# Relay_Driver_V1_1.net
KiCad netlist of a schematic drawn in EAGLE
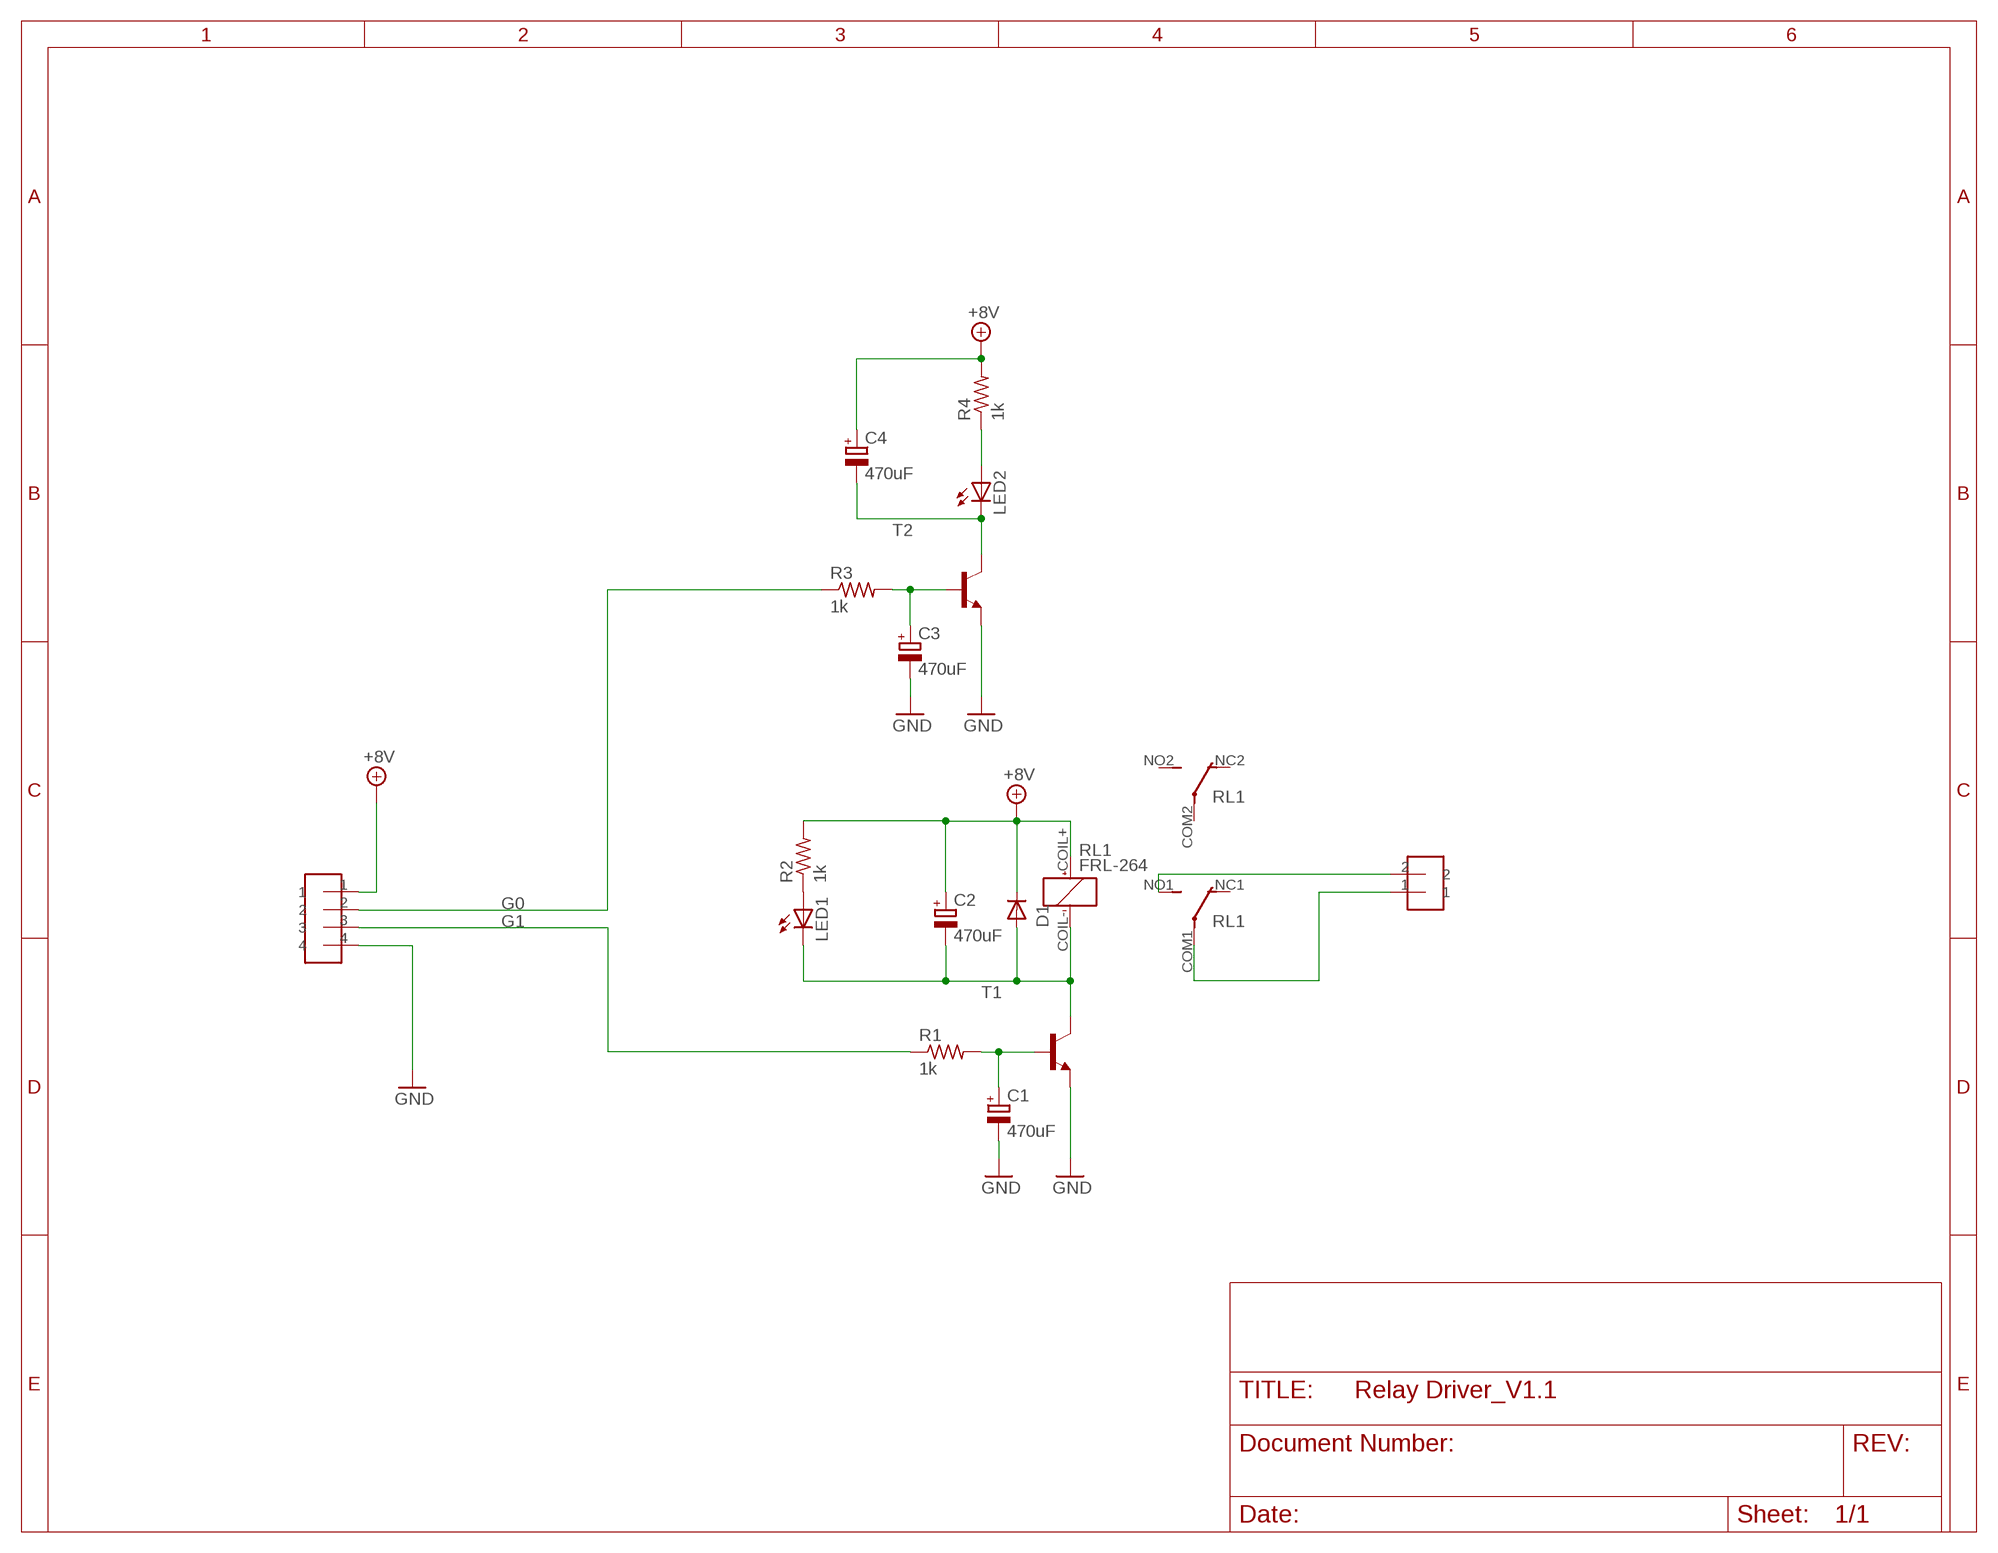
[diagram p0: schematic, sheet 1]

(export (version "E")
  (design (tool "Eeschema 10.0.6"))
  (components
    (comp (ref "C1")
      (value "470uF")
      (footprint "eagle-import:E3,5-10")
      (libsource (lib "eagle-import") (part "CPOL-EUE3.5-10"))
    )
    (comp (ref "C2")
      (value "470uF")
      (footprint "eagle-import:E3,5-10")
      (libsource (lib "eagle-import") (part "CPOL-EUE3.5-10"))
    )
    (comp (ref "C3")
      (value "470uF")
      (footprint "eagle-import:E3,5-10")
      (libsource (lib "eagle-import") (part "CPOL-EUE3.5-10"))
    )
    (comp (ref "C4")
      (value "470uF")
      (footprint "eagle-import:E3,5-10")
      (libsource (lib "eagle-import") (part "CPOL-EUE3.5-10"))
    )
    (comp (ref "D1")
      (value "1N4148DO35-10")
      (footprint "eagle-import:DO35-10")
      (libsource (lib "eagle-import") (part "1N4148DO35-10"))
    )
    (comp (ref "LED1")
      (value "LED5MM")
      (footprint "eagle-import:LED5MM")
      (libsource (lib "eagle-import") (part "LED5MM"))
    )
    (comp (ref "LED2")
      (value "LED5MM")
      (footprint "eagle-import:LED5MM")
      (libsource (lib "eagle-import") (part "LED5MM"))
    )
    (comp (ref "R1")
      (value "1k")
      (footprint "eagle-import:P0613V")
      (libsource (lib "eagle-import") (part "R-US_0613/5V"))
    )
    (comp (ref "R2")
      (value "1k")
      (footprint "eagle-import:P0613V")
      (libsource (lib "eagle-import") (part "R-US_0613/5V"))
    )
    (comp (ref "R3")
      (value "1k")
      (footprint "eagle-import:P0613V")
      (libsource (lib "eagle-import") (part "R-US_0613/5V"))
    )
    (comp (ref "R4")
      (value "1k")
      (footprint "eagle-import:P0613V")
      (libsource (lib "eagle-import") (part "R-US_0613/5V"))
    )
    (comp (ref "RL1")
      (value "FRL-264")
      (footprint "eagle-import:FRL-264")
      (libsource (lib "eagle-import") (part "FRL-264"))
    )
    (comp (ref "T1")
      (value "-NPN-TO92-EBC")
      (footprint "eagle-import:TO92-EBC")
      (libsource (lib "eagle-import") (part "-NPN-TO92-EBC"))
    )
    (comp (ref "T2")
      (value "-NPN-TO92-EBC")
      (footprint "eagle-import:TO92-EBC")
      (libsource (lib "eagle-import") (part "-NPN-TO92-EBC"))
    )
    (comp (ref "U$1")
      (value "1X4HEADER_100MIL")
      (footprint "eagle-import:1X4_100MIL")
      (libsource (lib "eagle-import") (part "1X4HEADER_100MIL"))
    )
    (comp (ref "U$2")
      (value "1X2HEADER_100MIL")
      (footprint "eagle-import:1X2_100MIL")
      (libsource (lib "eagle-import") (part "1X2HEADER_100MIL"))
    )
  )
  (nets
    (net (code "1") (name "+8V") (class "Default")
      (node (ref "C2") (pin "+") (pinfunction "+_+") (pintype "passive"))
      (node (ref "C4") (pin "+") (pinfunction "+_+") (pintype "passive"))
      (node (ref "D1") (pin "C") (pinfunction "C_C") (pintype "passive"))
      (node (ref "R2") (pin "2") (pinfunction "2_2") (pintype "passive"))
      (node (ref "R4") (pin "2") (pinfunction "2_2") (pintype "passive"))
      (node (ref "RL1") (pin "COIL+") (pinfunction "+_COIL+") (pintype "passive"))
      (node (ref "U$1") (pin "1") (pinfunction "1_1") (pintype "bidirectional"))
    )
    (net (code "2") (name "/G0") (class "Default")
      (node (ref "R3") (pin "1") (pinfunction "1_1") (pintype "passive"))
      (node (ref "U$1") (pin "2") (pinfunction "2_2") (pintype "bidirectional"))
    )
    (net (code "3") (name "/G1") (class "Default")
      (node (ref "R1") (pin "1") (pinfunction "1_1") (pintype "passive"))
      (node (ref "U$1") (pin "3") (pinfunction "3_3") (pintype "bidirectional"))
    )
    (net (code "4") (name "GND") (class "Default")
      (node (ref "C1") (pin "-") (pinfunction "-_-") (pintype "passive"))
      (node (ref "C3") (pin "-") (pinfunction "-_-") (pintype "passive"))
      (node (ref "T1") (pin "E") (pinfunction "E_E") (pintype "passive"))
      (node (ref "T2") (pin "E") (pinfunction "E_E") (pintype "passive"))
      (node (ref "U$1") (pin "4") (pinfunction "4_4") (pintype "bidirectional"))
    )
    (net (code "5") (name "Net-(C1-Pad+)") (class "Default")
      (node (ref "C1") (pin "+") (pinfunction "+_+") (pintype "passive"))
      (node (ref "R1") (pin "2") (pinfunction "2_2") (pintype "passive"))
      (node (ref "T1") (pin "B") (pinfunction "B_B") (pintype "passive"))
    )
    (net (code "6") (name "Net-(C3-Pad+)") (class "Default")
      (node (ref "C3") (pin "+") (pinfunction "+_+") (pintype "passive"))
      (node (ref "R3") (pin "2") (pinfunction "2_2") (pintype "passive"))
      (node (ref "T2") (pin "B") (pinfunction "B_B") (pintype "passive"))
    )
    (net (code "7") (name "Net-(LED1-C)") (class "Default")
      (node (ref "C2") (pin "-") (pinfunction "-_-") (pintype "passive"))
      (node (ref "D1") (pin "A") (pinfunction "A_A") (pintype "passive"))
      (node (ref "LED1") (pin "K") (pinfunction "C_K") (pintype "passive"))
      (node (ref "RL1") (pin "COIL-") (pinfunction "-_COIL-") (pintype "passive"))
      (node (ref "T1") (pin "C") (pinfunction "C_C") (pintype "passive"))
    )
    (net (code "8") (name "Net-(LED1-PadA)") (class "Default")
      (node (ref "LED1") (pin "A") (pinfunction "A_A") (pintype "passive"))
      (node (ref "R2") (pin "1") (pinfunction "1_1") (pintype "passive"))
    )
    (net (code "9") (name "Net-(LED2-C)") (class "Default")
      (node (ref "C4") (pin "-") (pinfunction "-_-") (pintype "passive"))
      (node (ref "LED2") (pin "K") (pinfunction "C_K") (pintype "passive"))
      (node (ref "T2") (pin "C") (pinfunction "C_C") (pintype "passive"))
    )
    (net (code "10") (name "Net-(LED2-PadA)") (class "Default")
      (node (ref "LED2") (pin "A") (pinfunction "A_A") (pintype "passive"))
      (node (ref "R4") (pin "1") (pinfunction "1_1") (pintype "passive"))
    )
    (net (code "11") (name "Net-(RL1B-P)") (class "Default")
      (node (ref "RL1") (pin "COM1") (pinfunction "P_COM1") (pintype "passive"))
      (node (ref "U$2") (pin "1") (pinfunction "1_1") (pintype "bidirectional"))
    )
    (net (code "12") (name "Net-(RL1B-S)") (class "Default")
      (node (ref "RL1") (pin "NO1") (pinfunction "S_NO1") (pintype "passive"))
      (node (ref "U$2") (pin "2") (pinfunction "2_2") (pintype "bidirectional"))
    )
    (net (code "13") (name "unconnected-(RL1B-O-PadNC1)") (class "Default")
      (node (ref "RL1") (pin "NC1") (pinfunction "O_NC1") (pintype "passive"))
    )
    (net (code "14") (name "unconnected-(RL1C-O-PadNC2)") (class "Default")
      (node (ref "RL1") (pin "NC2") (pinfunction "O_NC2") (pintype "passive"))
    )
    (net (code "15") (name "unconnected-(RL1C-P-PadCOM2)") (class "Default")
      (node (ref "RL1") (pin "COM2") (pinfunction "P_COM2") (pintype "passive"))
    )
    (net (code "16") (name "unconnected-(RL1C-S-PadNO2)") (class "Default")
      (node (ref "RL1") (pin "NO2") (pinfunction "S_NO2") (pintype "passive"))
    )
  )
)
